# H10R7_Backend.net
KiCad netlist of a schematic drawn in Altium Designer
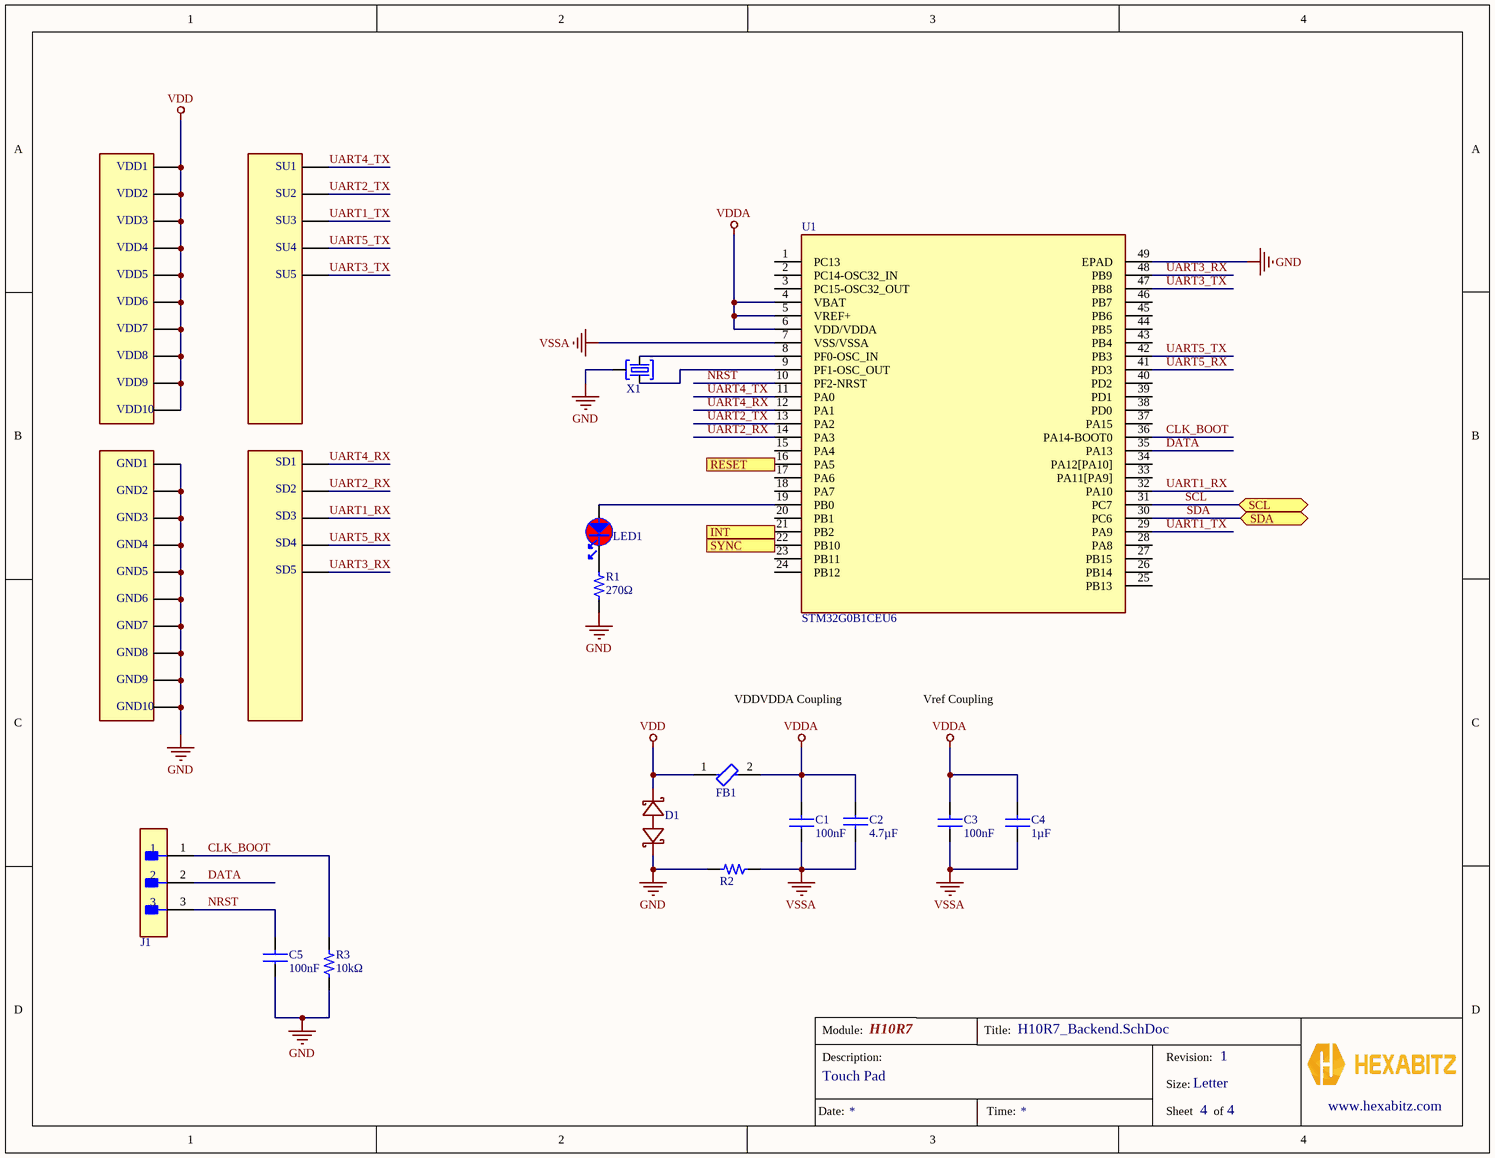
[diagram p0: H10R7_Backend.SchDoc]

(export (version "E")
  (design (tool "Eeschema 10.0.6"))
  (components
    (comp (ref "C1")
      (value "100nF")
      (footprint "C0603")
      (fields
        (field (name "MANUFACTURER") "Samsung Electro-Mechanics")
        (field (name "MANUFACTURER PART NUMBER") "CL10B104KA8NNNC")
        (field (name "TOLERANCE") "10%")
      )
      (libsource (lib "Hexabitz Altium Library") (part "generic Capacitor"))
    )
    (comp (ref "C2")
      (value "4.7µF")
      (footprint "C0805")
      (fields
        (field (name "MANUFACTURER") "Samsung Electro-Mechanics")
        (field (name "MANUFACTURER PART NUMBER") "CL21X475KAQNNNE")
        (field (name "TOLERANCE") "10%")
      )
      (libsource (lib "Hexabitz Altium Library") (part "generic Capacitor"))
    )
    (comp (ref "C3")
      (value "100nF")
      (footprint "C0603")
      (fields
        (field (name "MANUFACTURER") "Samsung Electro-Mechanics")
        (field (name "MANUFACTURER PART NUMBER") "CL10B104KA8NNNC")
        (field (name "TOLERANCE") "10%")
      )
      (libsource (lib "Hexabitz Altium Library") (part "generic Capacitor"))
    )
    (comp (ref "C4")
      (value "1µF")
      (footprint "C0805")
      (description "Ceramic Capacitor, Ceramic, 16V, 10% +Tol, 10% -Tol, X7R, 15% TC, 1uF, Surface Mount, 0805")
      (fields
        (field (name "MANUFACTURER") "Yageo Group")
        (field (name "MANUFACTURER PART NUMBER") "CC0805KKX7R7BB105")
      )
      (libsource (lib "Hexabitz Altium Library") (part "generic Capacitor"))
    )
    (comp (ref "C5")
      (value "100nF")
      (footprint "C0603")
      (fields
        (field (name "MANUFACTURER") "Samsung Electro-Mechanics")
        (field (name "MANUFACTURER PART NUMBER") "CL10B104KA8NNNC")
        (field (name "TOLERANCE") "10%")
      )
      (libsource (lib "Hexabitz Altium Library") (part "generic Capacitor"))
    )
    (comp (ref "D1")
      (value "CDSOD323-T03SC")
      (footprint "SOD2513X114N")
      (description "A 3V, 350W, bi-directional, standard capacitance, SOD323 pkg TVS Diode ¦ Bourns CDSOD323-T03SC")
      (fields (field (name "MANUFACTURER") "Bourns"))
      (libsource (lib "Hexabitz Altium Library") (part "CDSOD323-T03SC"))
    )
    (comp (ref "FB1")
      (value "MMZ1608Y300B")
      (footprint "FP-MMZ1608-0_8-MFG")
      (description "Ferrite Beads 0603 30ohms 1500mA Signal Line AEC-Q200")
      (fields
        (field (name "MANUFACTURER") "TDK")
        (field (name "MANUFACTURER PART NUMBER") "MMZ1608Y300BTD25")
      )
      (libsource (lib "Hexabitz Altium Library") (part "MMZ1608Y300B"))
    )
    (comp (ref "GND1")
      (value "HEXABIT_UART_PORT")
      (footprint "HEXABIT_POWER_PORT_D")
      (libsource (lib "hexabitz_connectors.Library") (part "HEXABIT_POWER_PORT_D"))
    )
    (comp (ref "GND2")
      (value "HEXABIT_UART_PORT")
      (footprint "HEXABIT_POWER_PORT_D")
      (libsource (lib "hexabitz_connectors.Library") (part "HEXABIT_POWER_PORT_D"))
    )
    (comp (ref "GND3")
      (value "HEXABIT_UART_PORT")
      (footprint "HEXABIT_POWER_PORT_D_300R")
      (libsource (lib "hexabitz_connectors.Library") (part "HEXABIT_POWER_PORT_D_300R"))
    )
    (comp (ref "GND4")
      (value "HEXABIT_UART_PORT")
      (footprint "HEXABIT_POWER_PORT_D")
      (libsource (lib "hexabitz_connectors.Library") (part "HEXABIT_POWER_PORT_D"))
    )
    (comp (ref "GND5")
      (value "HEXABIT_UART_PORT")
      (footprint "HEXABIT_POWER_PORT_D")
      (libsource (lib "hexabitz_connectors.Library") (part "HEXABIT_POWER_PORT_D"))
    )
    (comp (ref "GND6")
      (value "HEXABIT_UART_PORT")
      (footprint "HEXABIT_POWER_PORT_D")
      (libsource (lib "hexabitz_connectors.Library") (part "HEXABIT_POWER_PORT_D"))
    )
    (comp (ref "GND7")
      (value "HEXABIT_UART_PORT")
      (footprint "HEXABIT_POWER_PORT_D")
      (libsource (lib "hexabitz_connectors.Library") (part "HEXABIT_POWER_PORT_D"))
    )
    (comp (ref "GND8")
      (value "HEXABIT_UART_PORT")
      (footprint "HEXABIT_POWER_PORT_D_300L")
      (libsource (lib "hexabitz_connectors.Library") (part "HEXABIT_POWER_PORT_D_300L"))
    )
    (comp (ref "GND9")
      (value "HEXABIT_UART_PORT")
      (footprint "HEXABIT_POWER_PORT_D")
      (libsource (lib "hexabitz_connectors.Library") (part "HEXABIT_POWER_PORT_D"))
    )
    (comp (ref "GND10")
      (value "HEXABIT_UART_PORT")
      (footprint "HEXABIT_POWER_PORT_D")
      (libsource (lib "hexabitz_connectors.Library") (part "HEXABIT_POWER_PORT_D"))
    )
    (comp (ref "J1")
      (value "TSW-103-14-G-S")
      (footprint "FP-TSW-103-14-G-S-MFG")
      (description "CONN HEADER VERT 3POS 2.54MM")
      (libsource (lib "Altium Content Vault") (part "cd3439d6ef35ae5d9b27ec4fdd3e828"))
    )
    (comp (ref "LED1")
      (value "VLMS1300-GS08")
      (footprint "FP-6_541-5092_01-4-MFG")
      (description "LED Uni-Color Super Red 639nm 2-Pin Chip 0603(1608Metric) T/R")
      (fields (field (name "MANUFACTURER") "Vishay Semiconductors"))
      (libsource (lib "Hexabitz Altium Library") (part "VLMS1300-GS08"))
    )
    (comp (ref "R1")
      (value "270Ω")
      (footprint "R0603")
      (description "Res Thick Film 0603 270 Ohm 5% 0.1W(1/10W) ±200ppm/C Pad SMD Automotive T/R")
      (fields
        (field (name "MANUFACTURER") "Panasonic")
        (field (name "MANUFACTURER PART NUMBER") "ERJ-3GEYJ271V")
      )
      (libsource (lib "Hexabitz Altium Library") (part "generic Resistor"))
    )
    (comp (ref "R2")
      (value "Manufacturer Part Number")
      (footprint "R0603")
      (libsource (lib "") (part "generic Resistor_1"))
    )
    (comp (ref "R3")
      (value "10kΩ")
      (footprint "R0603")
      (description "100mW Thick Film Resistors ±100ppm/℃ ±1% 10kΩ 0603 Chip Resistor - Surface Mount ROHS")
      (fields
        (field (name "MANUFACTURER") "Yageo Group")
        (field (name "MANUFACTURER PART NUMBER") "RC0603FR-0710KL")
      )
      (libsource (lib "") (part "generic Resistor_2"))
    )
    (comp (ref "SD1")
      (value "HEXABIT_UART_PORT")
      (footprint "HEXABIT_UART_PORT_D")
      (libsource (lib "hexabitz_connectors.Library") (part "HEXABIT_UART_PORT_D"))
    )
    (comp (ref "SD2")
      (value "HEXABIT_UART_PORT")
      (footprint "HEXABIT_UART_PORT_D")
      (libsource (lib "hexabitz_connectors.Library") (part "HEXABIT_UART_PORT_D"))
    )
    (comp (ref "SD3")
      (value "HEXABIT_UART_PORT")
      (footprint "HEXABIT_UART_PORT_D")
      (libsource (lib "hexabitz_connectors.Library") (part "HEXABIT_UART_PORT_D"))
    )
    (comp (ref "SD4")
      (value "HEXABIT_UART_PORT")
      (footprint "HEXABIT_UART_PORT_D")
      (libsource (lib "hexabitz_connectors.Library") (part "HEXABIT_UART_PORT_D"))
    )
    (comp (ref "SD5")
      (value "HEXABIT_UART_PORT")
      (footprint "HEXABIT_UART_PORT_D")
      (libsource (lib "hexabitz_connectors.Library") (part "HEXABIT_UART_PORT_D"))
    )
    (comp (ref "SU1")
      (value "HEXABIT_UART_PORT")
      (footprint "HEXABIT_UART_PORT_U")
      (libsource (lib "hexabitz_connectors.Library") (part "HEXABIT_UART_PORT_U"))
    )
    (comp (ref "SU2")
      (value "HEXABIT_UART_PORT")
      (footprint "HEXABIT_UART_PORT_U")
      (libsource (lib "hexabitz_connectors.Library") (part "HEXABIT_UART_PORT_U"))
    )
    (comp (ref "SU3")
      (value "HEXABIT_UART_PORT")
      (footprint "HEXABIT_UART_PORT_U")
      (libsource (lib "hexabitz_connectors.Library") (part "HEXABIT_UART_PORT_U"))
    )
    (comp (ref "SU4")
      (value "HEXABIT_UART_PORT")
      (footprint "HEXABIT_UART_PORT_U")
      (libsource (lib "hexabitz_connectors.Library") (part "HEXABIT_UART_PORT_U"))
    )
    (comp (ref "SU5")
      (value "HEXABIT_UART_PORT")
      (footprint "HEXABIT_UART_PORT_U")
      (libsource (lib "hexabitz_connectors.Library") (part "HEXABIT_UART_PORT_U"))
    )
    (comp (ref "U1")
      (value "~")
      (footprint "QFN50P700X700X65-49N-D")
      (description "MCU 32-bit ARM Cortex M0+ RISC 512KB Flash 1.8V/2.5V/3.3V 48-Pin UFQFPN EP Tray")
      (fields
        (field (name "MANUFACTURER") "STMicroelectronics")
        (field (name "MANUFACTURER PART NUMBER") "STM32G0B1CEU6")
      )
      (libsource (lib "Hexabitz Altium Library (1)") (part "STM32G0B1CEU6"))
    )
    (comp (ref "VDD1")
      (value "HEXABIT_UART_PORT")
      (footprint "HEXABIT_POWER_PORT_U")
      (libsource (lib "hexabitz_connectors.Library") (part "HEXABIT_POWER_PORT_U"))
    )
    (comp (ref "VDD2")
      (value "HEXABIT_UART_PORT")
      (footprint "HEXABIT_POWER_PORT_U")
      (libsource (lib "hexabitz_connectors.Library") (part "HEXABIT_POWER_PORT_U"))
    )
    (comp (ref "VDD3")
      (value "HEXABIT_UART_PORT")
      (footprint "HEXABIT_POWER_PORT_U_300R")
      (libsource (lib "hexabitz_connectors.Library") (part "HEXABIT_POWER_PORT_U_300R"))
    )
    (comp (ref "VDD4")
      (value "HEXABIT_UART_PORT")
      (footprint "HEXABIT_POWER_PORT_U")
      (libsource (lib "hexabitz_connectors.Library") (part "HEXABIT_POWER_PORT_U"))
    )
    (comp (ref "VDD5")
      (value "HEXABIT_UART_PORT")
      (footprint "HEXABIT_POWER_PORT_U")
      (libsource (lib "hexabitz_connectors.Library") (part "HEXABIT_POWER_PORT_U"))
    )
    (comp (ref "VDD6")
      (value "HEXABIT_UART_PORT")
      (footprint "HEXABIT_POWER_PORT_U")
      (libsource (lib "hexabitz_connectors.Library") (part "HEXABIT_POWER_PORT_U"))
    )
    (comp (ref "VDD7")
      (value "HEXABIT_UART_PORT")
      (footprint "HEXABIT_POWER_PORT_U")
      (libsource (lib "hexabitz_connectors.Library") (part "HEXABIT_POWER_PORT_U"))
    )
    (comp (ref "VDD8")
      (value "HEXABIT_UART_PORT")
      (footprint "HEXABIT_POWER_PORT_U_300L")
      (libsource (lib "hexabitz_connectors.Library") (part "HEXABIT_POWER_PORT_U_300L"))
    )
    (comp (ref "VDD9")
      (value "HEXABIT_UART_PORT")
      (footprint "HEXABIT_POWER_PORT_U")
      (libsource (lib "hexabitz_connectors.Library") (part "HEXABIT_POWER_PORT_U"))
    )
    (comp (ref "VDD10")
      (value "HEXABIT_UART_PORT")
      (footprint "HEXABIT_POWER_PORT_U")
      (libsource (lib "hexabitz_connectors.Library") (part "HEXABIT_POWER_PORT_U"))
    )
    (comp (ref "X1")
      (value "CSTCE8M00G52Z-R0")
      (footprint "XTALL_CSTCE8M00G52")
      (description "Ceramic Resonator 8MHz ±0.5% (Tol) ±0.2% (Stability) 10pF 40Ohm 3-Pin CSMD T/R")
      (fields (field (name "MANUFACTURER") "Murata") (field (name "TOLERANCE") "0.5%"))
      (libsource (lib "Hexabitz Altium Library") (part "CSTCE8M00G52Z-R0"))
    )
  )
  (nets
    (net (code "1") (name "/CLK_BOOT") (class "Default")
      (node (ref "J1") (pin "1") (pinfunction "1_1") (pintype "passive"))
      (node (ref "R3") (pin "1") (pinfunction "1_1") (pintype "passive"))
      (node (ref "U1") (pin "36") (pinfunction "PA14-BOOT0_36") (pintype "passive"))
    )
    (net (code "2") (name "/DATA") (class "Default")
      (node (ref "J1") (pin "2") (pinfunction "2_2") (pintype "passive"))
      (node (ref "U1") (pin "35") (pinfunction "PA13_35") (pintype "passive"))
    )
    (net (code "3") (name "/INT") (class "Default")
      (node (ref "U1") (pin "21") (pinfunction "PB2_21") (pintype "passive"))
    )
    (net (code "4") (name "/NRST") (class "Default")
      (node (ref "C5") (pin "2") (pinfunction "2_2") (pintype "passive"))
      (node (ref "J1") (pin "3") (pinfunction "3_3") (pintype "passive"))
      (node (ref "U1") (pin "10") (pinfunction "PF2-NRST_10") (pintype "passive"))
    )
    (net (code "5") (name "/RESET") (class "Default")
      (node (ref "U1") (pin "16") (pinfunction "PA5_16") (pintype "passive"))
    )
    (net (code "6") (name "/SCL") (class "Default")
      (node (ref "U1") (pin "31") (pinfunction "PC7_31") (pintype "passive"))
    )
    (net (code "7") (name "/SDA") (class "Default")
      (node (ref "U1") (pin "30") (pinfunction "PC6_30") (pintype "passive"))
    )
    (net (code "8") (name "/SYNC") (class "Default")
      (node (ref "U1") (pin "22") (pinfunction "PB10_22") (pintype "passive"))
    )
    (net (code "9") (name "/UART1_RX") (class "Default")
      (node (ref "SD3") (pin "UART_D") (pinfunction "UART_D_UART_D") (pintype "passive"))
      (node (ref "U1") (pin "32") (pinfunction "PA10_32") (pintype "passive"))
    )
    (net (code "10") (name "/UART1_TX") (class "Default")
      (node (ref "SU3") (pin "UART_U") (pinfunction "UART_U_UART_U") (pintype "passive"))
      (node (ref "U1") (pin "29") (pinfunction "PA9_29") (pintype "passive"))
    )
    (net (code "11") (name "/UART2_RX") (class "Default")
      (node (ref "SD2") (pin "UART_D") (pinfunction "UART_D_UART_D") (pintype "passive"))
      (node (ref "U1") (pin "14") (pinfunction "PA3_14") (pintype "passive"))
    )
    (net (code "12") (name "/UART2_TX") (class "Default")
      (node (ref "SU2") (pin "UART_U") (pinfunction "UART_U_UART_U") (pintype "passive"))
      (node (ref "U1") (pin "13") (pinfunction "PA2_13") (pintype "passive"))
    )
    (net (code "13") (name "/UART3_RX") (class "Default")
      (node (ref "SD5") (pin "UART_D") (pinfunction "UART_D_UART_D") (pintype "passive"))
      (node (ref "U1") (pin "48") (pinfunction "PB9_48") (pintype "passive"))
    )
    (net (code "14") (name "/UART3_TX") (class "Default")
      (node (ref "SU5") (pin "UART_U") (pinfunction "UART_U_UART_U") (pintype "passive"))
      (node (ref "U1") (pin "47") (pinfunction "PB8_47") (pintype "passive"))
    )
    (net (code "15") (name "/UART4_RX") (class "Default")
      (node (ref "SD1") (pin "UART_D") (pinfunction "UART_D_UART_D") (pintype "passive"))
      (node (ref "U1") (pin "12") (pinfunction "PA1_12") (pintype "passive"))
    )
    (net (code "16") (name "/UART4_TX") (class "Default")
      (node (ref "SU1") (pin "UART_U") (pinfunction "UART_U_UART_U") (pintype "passive"))
      (node (ref "U1") (pin "11") (pinfunction "PA0_11") (pintype "passive"))
    )
    (net (code "17") (name "/UART5_RX") (class "Default")
      (node (ref "SD4") (pin "UART_D") (pinfunction "UART_D_UART_D") (pintype "passive"))
      (node (ref "U1") (pin "41") (pinfunction "PD3_41") (pintype "passive"))
    )
    (net (code "18") (name "/UART5_TX") (class "Default")
      (node (ref "SU4") (pin "UART_U") (pinfunction "UART_U_UART_U") (pintype "passive"))
      (node (ref "U1") (pin "42") (pinfunction "PB3_42") (pintype "passive"))
    )
    (net (code "19") (name "GND") (class "Default")
      (node (ref "C5") (pin "1") (pinfunction "1_1") (pintype "passive"))
      (node (ref "D1") (pin "1") (pinfunction "A_1") (pintype "passive"))
      (node (ref "GND1") (pin "Pwr_D") (pinfunction "Pwr_D_Pwr_D") (pintype "passive"))
      (node (ref "GND10") (pin "Pwr_D") (pinfunction "Pwr_D_Pwr_D") (pintype "passive"))
      (node (ref "GND2") (pin "Pwr_D") (pinfunction "Pwr_D_Pwr_D") (pintype "passive"))
      (node (ref "GND3") (pin "Pwr_D") (pinfunction "Pwr_D_Pwr_D") (pintype "passive"))
      (node (ref "GND4") (pin "Pwr_D") (pinfunction "Pwr_D_Pwr_D") (pintype "passive"))
      (node (ref "GND5") (pin "Pwr_D") (pinfunction "Pwr_D_Pwr_D") (pintype "passive"))
      (node (ref "GND6") (pin "Pwr_D") (pinfunction "Pwr_D_Pwr_D") (pintype "passive"))
      (node (ref "GND7") (pin "Pwr_D") (pinfunction "Pwr_D_Pwr_D") (pintype "passive"))
      (node (ref "GND8") (pin "Pwr_D") (pinfunction "Pwr_D_Pwr_D") (pintype "passive"))
      (node (ref "GND9") (pin "Pwr_D") (pinfunction "Pwr_D_Pwr_D") (pintype "passive"))
      (node (ref "R1") (pin "1") (pinfunction "1_1") (pintype "passive"))
      (node (ref "R2") (pin "1") (pinfunction "1_1") (pintype "passive"))
      (node (ref "R3") (pin "2") (pinfunction "2_2") (pintype "passive"))
      (node (ref "U1") (pin "49") (pinfunction "EPAD_49") (pintype "passive"))
      (node (ref "X1") (pin "P$2") (pinfunction "2_P$2") (pintype "passive"))
    )
    (net (code "20") (name "Net-(LED1-Pad1)") (class "Default")
      (node (ref "LED1") (pin "1") (pintype "passive"))
      (node (ref "R1") (pin "2") (pinfunction "2_2") (pintype "passive"))
    )
    (net (code "21") (name "Net-(U1-PB0)") (class "Default")
      (node (ref "LED1") (pin "2") (pintype "passive"))
      (node (ref "U1") (pin "19") (pinfunction "PB0_19") (pintype "passive"))
    )
    (net (code "22") (name "Net-(U1-PF0-OSC_IN)") (class "Default")
      (node (ref "U1") (pin "8") (pinfunction "PF0-OSC_IN_8") (pintype "passive"))
      (node (ref "X1") (pin "P$3") (pinfunction "3_P$3") (pintype "passive"))
    )
    (net (code "23") (name "Net-(U1-PF1-OSC_OUT)") (class "Default")
      (node (ref "U1") (pin "9") (pinfunction "PF1-OSC_OUT_9") (pintype "passive"))
      (node (ref "X1") (pin "P$1") (pinfunction "1_P$1") (pintype "passive"))
    )
    (net (code "24") (name "VDD") (class "Default")
      (node (ref "D1") (pin "2") (pinfunction "C_2") (pintype "passive"))
      (node (ref "FB1") (pin "1") (pinfunction "1_1") (pintype "passive"))
      (node (ref "VDD1") (pin "Pwr_U") (pinfunction "Pwr_U_Pwr_U") (pintype "passive"))
      (node (ref "VDD10") (pin "Pwr_U") (pinfunction "Pwr_U_Pwr_U") (pintype "passive"))
      (node (ref "VDD2") (pin "Pwr_U") (pinfunction "Pwr_U_Pwr_U") (pintype "passive"))
      (node (ref "VDD3") (pin "Pwr_U") (pinfunction "Pwr_U_Pwr_U") (pintype "passive"))
      (node (ref "VDD4") (pin "Pwr_U") (pinfunction "Pwr_U_Pwr_U") (pintype "passive"))
      (node (ref "VDD5") (pin "Pwr_U") (pinfunction "Pwr_U_Pwr_U") (pintype "passive"))
      (node (ref "VDD6") (pin "Pwr_U") (pinfunction "Pwr_U_Pwr_U") (pintype "passive"))
      (node (ref "VDD7") (pin "Pwr_U") (pinfunction "Pwr_U_Pwr_U") (pintype "passive"))
      (node (ref "VDD8") (pin "Pwr_U") (pinfunction "Pwr_U_Pwr_U") (pintype "passive"))
      (node (ref "VDD9") (pin "Pwr_U") (pinfunction "Pwr_U_Pwr_U") (pintype "passive"))
    )
    (net (code "25") (name "VDDA") (class "Default")
      (node (ref "C1") (pin "2") (pinfunction "2_2") (pintype "passive"))
      (node (ref "C2") (pin "1") (pinfunction "1_1") (pintype "passive"))
      (node (ref "C3") (pin "2") (pinfunction "2_2") (pintype "passive"))
      (node (ref "C4") (pin "2") (pinfunction "2_2") (pintype "passive"))
      (node (ref "FB1") (pin "2") (pinfunction "2_2") (pintype "passive"))
      (node (ref "U1") (pin "4") (pinfunction "VBAT_4") (pintype "passive"))
      (node (ref "U1") (pin "5") (pinfunction "VREF+_5") (pintype "passive"))
      (node (ref "U1") (pin "6") (pinfunction "VDD/VDDA_6") (pintype "passive"))
    )
    (net (code "26") (name "VSSA") (class "Default")
      (node (ref "C1") (pin "1") (pinfunction "1_1") (pintype "passive"))
      (node (ref "C2") (pin "2") (pinfunction "2_2") (pintype "passive"))
      (node (ref "C3") (pin "1") (pinfunction "1_1") (pintype "passive"))
      (node (ref "C4") (pin "1") (pinfunction "1_1") (pintype "passive"))
      (node (ref "R2") (pin "2") (pinfunction "2_2") (pintype "passive"))
      (node (ref "U1") (pin "7") (pinfunction "VSS/VSSA_7") (pintype "passive"))
    )
    (net (code "27") (name "unconnected-(U1-PA4-Pad15)") (class "Default")
      (node (ref "U1") (pin "15") (pinfunction "PA4_15") (pintype "passive"))
    )
    (net (code "28") (name "unconnected-(U1-PA6-Pad17)") (class "Default")
      (node (ref "U1") (pin "17") (pinfunction "PA6_17") (pintype "passive"))
    )
    (net (code "29") (name "unconnected-(U1-PA7-Pad18)") (class "Default")
      (node (ref "U1") (pin "18") (pinfunction "PA7_18") (pintype "passive"))
    )
    (net (code "30") (name "unconnected-(U1-PA8-Pad28)") (class "Default")
      (node (ref "U1") (pin "28") (pinfunction "PA8_28") (pintype "passive"))
    )
    (net (code "31") (name "unconnected-(U1-PA11[PA9]-Pad33)") (class "Default")
      (node (ref "U1") (pin "33") (pinfunction "PA11[PA9]_33") (pintype "passive"))
    )
    (net (code "32") (name "unconnected-(U1-PA12[PA10]-Pad34)") (class "Default")
      (node (ref "U1") (pin "34") (pinfunction "PA12[PA10]_34") (pintype "passive"))
    )
    (net (code "33") (name "unconnected-(U1-PA15-Pad37)") (class "Default")
      (node (ref "U1") (pin "37") (pinfunction "PA15_37") (pintype "passive"))
    )
    (net (code "34") (name "unconnected-(U1-PB1-Pad20)") (class "Default")
      (node (ref "U1") (pin "20") (pinfunction "PB1_20") (pintype "passive"))
    )
    (net (code "35") (name "unconnected-(U1-PB4-Pad43)") (class "Default")
      (node (ref "U1") (pin "43") (pinfunction "PB4_43") (pintype "passive"))
    )
    (net (code "36") (name "unconnected-(U1-PB5-Pad44)") (class "Default")
      (node (ref "U1") (pin "44") (pinfunction "PB5_44") (pintype "passive"))
    )
    (net (code "37") (name "unconnected-(U1-PB6-Pad45)") (class "Default")
      (node (ref "U1") (pin "45") (pinfunction "PB6_45") (pintype "passive"))
    )
    (net (code "38") (name "unconnected-(U1-PB7-Pad46)") (class "Default")
      (node (ref "U1") (pin "46") (pinfunction "PB7_46") (pintype "passive"))
    )
    (net (code "39") (name "unconnected-(U1-PB11-Pad23)") (class "Default")
      (node (ref "U1") (pin "23") (pinfunction "PB11_23") (pintype "passive"))
    )
    (net (code "40") (name "unconnected-(U1-PB12-Pad24)") (class "Default")
      (node (ref "U1") (pin "24") (pinfunction "PB12_24") (pintype "passive"))
    )
    (net (code "41") (name "unconnected-(U1-PB13-Pad25)") (class "Default")
      (node (ref "U1") (pin "25") (pinfunction "PB13_25") (pintype "passive"))
    )
    (net (code "42") (name "unconnected-(U1-PB14-Pad26)") (class "Default")
      (node (ref "U1") (pin "26") (pinfunction "PB14_26") (pintype "passive"))
    )
    (net (code "43") (name "unconnected-(U1-PB15-Pad27)") (class "Default")
      (node (ref "U1") (pin "27") (pinfunction "PB15_27") (pintype "passive"))
    )
    (net (code "44") (name "unconnected-(U1-PC13-Pad1)") (class "Default")
      (node (ref "U1") (pin "1") (pinfunction "PC13_1") (pintype "passive"))
    )
    (net (code "45") (name "unconnected-(U1-PC14-OSC32_IN-Pad2)") (class "Default")
      (node (ref "U1") (pin "2") (pinfunction "PC14-OSC32_IN_2") (pintype "passive"))
    )
    (net (code "46") (name "unconnected-(U1-PC15-OSC32_OUT-Pad3)") (class "Default")
      (node (ref "U1") (pin "3") (pinfunction "PC15-OSC32_OUT_3") (pintype "passive"))
    )
    (net (code "47") (name "unconnected-(U1-PD0-Pad38)") (class "Default")
      (node (ref "U1") (pin "38") (pinfunction "PD0_38") (pintype "passive"))
    )
    (net (code "48") (name "unconnected-(U1-PD1-Pad39)") (class "Default")
      (node (ref "U1") (pin "39") (pinfunction "PD1_39") (pintype "passive"))
    )
    (net (code "49") (name "unconnected-(U1-PD2-Pad40)") (class "Default")
      (node (ref "U1") (pin "40") (pinfunction "PD2_40") (pintype "passive"))
    )
  )
)
